# BK5811.net
KiCad netlist of a schematic drawn in Altium Designer
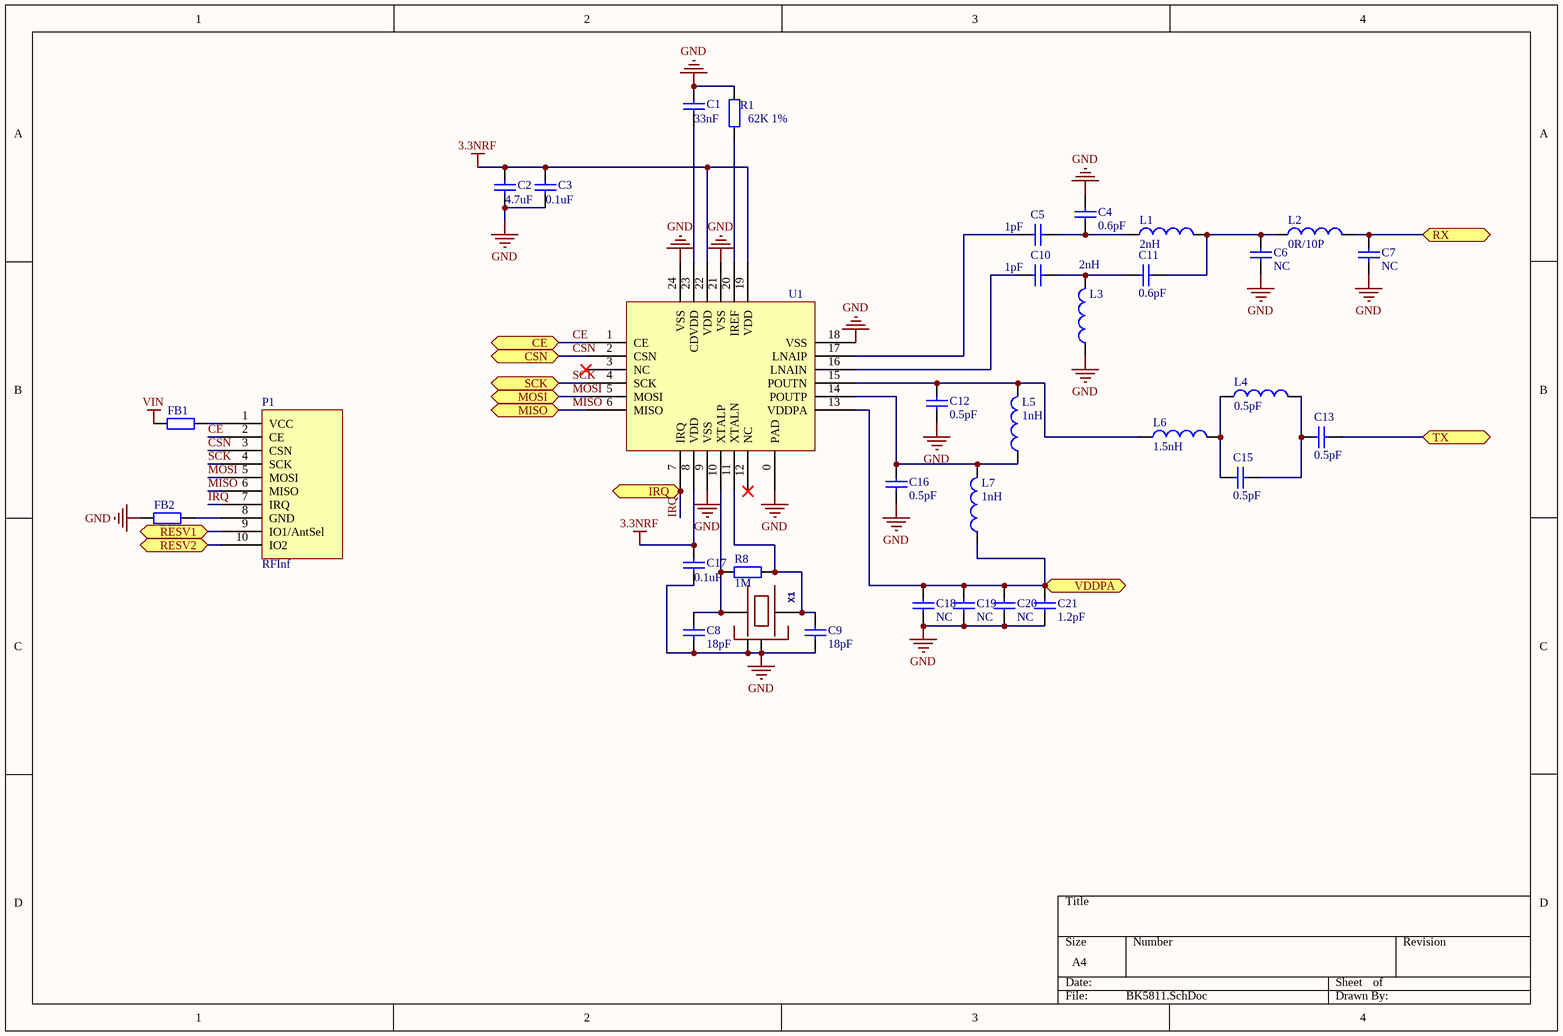
[diagram p0: BK5811.SchDoc]

(export (version "E")
  (design (tool "Eeschema 10.0.6"))
  (components
    (comp (ref "C1")
      (value "33nF")
      (footprint "0402")
      (description "Capacitor")
      (fields (field (name "PUBLISHER") "Altium Limited"))
      (libsource (lib "RTC6705") (part "Cap"))
    )
    (comp (ref "C2")
      (value "4.7uF")
      (footprint "0603")
      (description "Capacitor")
      (fields (field (name "PUBLISHER") "Altium Limited"))
      (libsource (lib "RTC6705") (part "Cap"))
    )
    (comp (ref "C3")
      (value "0.1uF")
      (footprint "0402")
      (description "Capacitor")
      (fields (field (name "PUBLISHER") "Altium Limited"))
      (libsource (lib "RTC6705") (part "Cap"))
    )
    (comp (ref "C4")
      (value "0.6pF")
      (footprint "0402")
      (description "Capacitor")
      (fields (field (name "PUBLISHER") "Altium Limited"))
      (libsource (lib "RTC6705") (part "Cap"))
    )
    (comp (ref "C5")
      (value "1pF")
      (footprint "0402")
      (description "Capacitor")
      (fields (field (name "PUBLISHER") "Altium Limited"))
      (libsource (lib "RTC6705") (part "Cap"))
    )
    (comp (ref "C6")
      (value "NC")
      (footprint "0402")
      (description "Capacitor")
      (fields (field (name "PUBLISHER") "Altium Limited"))
      (libsource (lib "RTC6705") (part "Cap"))
    )
    (comp (ref "C7")
      (value "NC")
      (footprint "0402")
      (description "Capacitor")
      (fields (field (name "PUBLISHER") "Altium Limited"))
      (libsource (lib "RTC6705") (part "Cap"))
    )
    (comp (ref "C8")
      (value "18pF")
      (footprint "0402")
      (description "Capacitor")
      (fields (field (name "Comment") "Cap") (field (name "PUBLISHER") "Altium Limited"))
      (libsource (lib "RTC6705") (part "Cap"))
    )
    (comp (ref "C9")
      (value "18pF")
      (footprint "0402")
      (description "Capacitor")
      (fields (field (name "Comment") "Cap") (field (name "PUBLISHER") "Altium Limited"))
      (libsource (lib "RTC6705") (part "Cap"))
    )
    (comp (ref "C10")
      (value "1pF")
      (footprint "0402")
      (description "Capacitor")
      (fields (field (name "PUBLISHER") "Altium Limited"))
      (libsource (lib "RTC6705") (part "Cap"))
    )
    (comp (ref "C11")
      (value "0.6pF")
      (footprint "0402")
      (description "Capacitor")
      (fields (field (name "PUBLISHER") "Altium Limited"))
      (libsource (lib "RTC6705") (part "Cap"))
    )
    (comp (ref "C12")
      (value "0.5pF")
      (footprint "0402")
      (description "Capacitor")
      (fields (field (name "PUBLISHER") "Altium Limited"))
      (libsource (lib "RTC6705") (part "Cap"))
    )
    (comp (ref "C13")
      (value "0.5pF")
      (footprint "0402")
      (description "Capacitor")
      (fields (field (name "PUBLISHER") "Altium Limited"))
      (libsource (lib "RTC6705") (part "Cap"))
    )
    (comp (ref "C15")
      (value "0.5pF")
      (footprint "0402")
      (description "Capacitor")
      (fields (field (name "PUBLISHER") "Altium Limited"))
      (libsource (lib "RTC6705") (part "Cap"))
    )
    (comp (ref "C16")
      (value "0.5pF")
      (footprint "0402")
      (description "Capacitor")
      (fields (field (name "PUBLISHER") "Altium Limited"))
      (libsource (lib "RTC6705") (part "Cap"))
    )
    (comp (ref "C17")
      (value "0.1uF")
      (footprint "0402")
      (description "Capacitor")
      (fields (field (name "PUBLISHER") "Altium Limited"))
      (libsource (lib "RTC6705") (part "Cap"))
    )
    (comp (ref "C18")
      (value "NC")
      (footprint "0402")
      (description "Capacitor")
      (fields (field (name "PUBLISHER") "Altium Limited"))
      (libsource (lib "RTC6705") (part "Cap"))
    )
    (comp (ref "C19")
      (value "NC")
      (footprint "0402")
      (description "Capacitor")
      (fields (field (name "PUBLISHER") "Altium Limited"))
      (libsource (lib "RTC6705") (part "Cap"))
    )
    (comp (ref "C20")
      (value "NC")
      (footprint "0402")
      (description "Capacitor")
      (fields (field (name "PUBLISHER") "Altium Limited"))
      (libsource (lib "RTC6705") (part "Cap"))
    )
    (comp (ref "C21")
      (value "1.2pF")
      (footprint "0402")
      (description "Capacitor")
      (fields (field (name "PUBLISHER") "Altium Limited"))
      (libsource (lib "RTC6705") (part "Cap"))
    )
    (comp (ref "FB1")
      (value "Res2")
      (footprint "0402")
      (description "Resistor")
      (fields (field (name "PUBLISHER") "Altium Limited"))
      (libsource (lib "RTC6705") (part "Res2"))
    )
    (comp (ref "FB2")
      (value "Res2")
      (footprint "0402")
      (description "Resistor")
      (fields (field (name "PUBLISHER") "Altium Limited"))
      (libsource (lib "RTC6705") (part "Res2"))
    )
    (comp (ref "L1")
      (value "2nH")
      (footprint "0402")
      (description "Inductor")
      (fields (field (name "PUBLISHER") "Altium Limited"))
      (libsource (lib "Miscellaneous Devices") (part "Inductor"))
    )
    (comp (ref "L2")
      (value "0R/10P")
      (footprint "0402")
      (description "Inductor")
      (fields (field (name "PUBLISHER") "Altium Limited"))
      (libsource (lib "Miscellaneous Devices") (part "Inductor"))
    )
    (comp (ref "L3")
      (value "2nH")
      (footprint "0402")
      (description "Inductor")
      (fields (field (name "PUBLISHER") "Altium Limited"))
      (libsource (lib "Miscellaneous Devices") (part "Inductor"))
    )
    (comp (ref "L4")
      (value "0.5pF")
      (footprint "0402")
      (description "Inductor")
      (fields (field (name "PUBLISHER") "Altium Limited"))
      (libsource (lib "Miscellaneous Devices") (part "Inductor"))
    )
    (comp (ref "L5")
      (value "1nH")
      (footprint "0402")
      (description "Inductor")
      (fields (field (name "PUBLISHER") "Altium Limited"))
      (libsource (lib "Miscellaneous Devices") (part "Inductor"))
    )
    (comp (ref "L6")
      (value "1.5nH")
      (footprint "0402")
      (description "Inductor")
      (fields (field (name "PUBLISHER") "Altium Limited"))
      (libsource (lib "Miscellaneous Devices") (part "Inductor"))
    )
    (comp (ref "L7")
      (value "1nH")
      (footprint "0402")
      (description "Inductor")
      (fields (field (name "PUBLISHER") "Altium Limited"))
      (libsource (lib "Miscellaneous Devices") (part "Inductor"))
    )
    (comp (ref "P1")
      (value "RFInf")
      (footprint "RFInf - SINGLESIDE")
      (libsource (lib "NRF24L01_PA") (part "RFInf"))
    )
    (comp (ref "R1")
      (value "62K 1%")
      (footprint "0402")
      (description "Resistor")
      (fields (field (name "PUBLISHER") "Altium Limited"))
      (libsource (lib "") (part "Res2_1"))
    )
    (comp (ref "R8")
      (value "1M")
      (footprint "0402")
      (description "Resistor")
      (fields (field (name "Comment") "Res2") (field (name "PUBLISHER") "Altium Limited"))
      (libsource (lib "") (part "Res2_2"))
    )
    (comp (ref "U1") (value "BK5811") (footprint "BK5811") (libsource (lib "BK5811") (part "BK5811")))
    (comp (ref "X1")
      (value "16Mhz")
      (footprint "OSCILLATOR-3.2X2.5")
      (description "Crystal Oscillator in 3.2x2.5 SMD")
      (libsource (lib "pixhawk2") (part "OSCILLATOR-3.2X2.5"))
    )
  )
  (nets
    (net (code "1") (name "/CE") (class "Default")
      (node (ref "P1") (pin "2") (pinfunction "CE_2") (pintype "passive"))
      (node (ref "U1") (pin "1") (pinfunction "CE_1") (pintype "passive"))
    )
    (net (code "2") (name "/CSN") (class "Default")
      (node (ref "P1") (pin "3") (pinfunction "CSN_3") (pintype "passive"))
      (node (ref "U1") (pin "2") (pinfunction "CSN_2") (pintype "passive"))
    )
    (net (code "3") (name "/IRQ") (class "Default")
      (node (ref "P1") (pin "7") (pinfunction "IRQ_7") (pintype "passive"))
      (node (ref "U1") (pin "7") (pinfunction "IRQ_7") (pintype "passive"))
    )
    (net (code "4") (name "/MISO") (class "Default")
      (node (ref "P1") (pin "6") (pinfunction "MISO_6") (pintype "passive"))
      (node (ref "U1") (pin "6") (pinfunction "MISO_6") (pintype "passive"))
    )
    (net (code "5") (name "/MOSI") (class "Default")
      (node (ref "P1") (pin "5") (pinfunction "MOSI_5") (pintype "passive"))
      (node (ref "U1") (pin "5") (pinfunction "MOSI_5") (pintype "passive"))
    )
    (net (code "6") (name "/RESV1") (class "Default")
      (node (ref "P1") (pin "9") (pinfunction "IO1/AntSel_9") (pintype "passive"))
    )
    (net (code "7") (name "/RESV2") (class "Default")
      (node (ref "P1") (pin "10") (pinfunction "IO2_10") (pintype "passive"))
    )
    (net (code "8") (name "/RX") (class "Default")
      (node (ref "C7") (pin "2") (pinfunction "2_2") (pintype "passive"))
      (node (ref "L2") (pin "2") (pinfunction "2_2") (pintype "passive"))
    )
    (net (code "9") (name "/SCK") (class "Default")
      (node (ref "P1") (pin "4") (pinfunction "SCK_4") (pintype "passive"))
      (node (ref "U1") (pin "4") (pinfunction "SCK_4") (pintype "passive"))
    )
    (net (code "10") (name "/TX") (class "Default")
      (node (ref "C13") (pin "2") (pinfunction "2_2") (pintype "passive"))
    )
    (net (code "11") (name "/VDDPA") (class "Default")
      (node (ref "C18") (pin "1") (pinfunction "1_1") (pintype "passive"))
      (node (ref "C19") (pin "1") (pinfunction "1_1") (pintype "passive"))
      (node (ref "C20") (pin "1") (pinfunction "1_1") (pintype "passive"))
      (node (ref "C21") (pin "1") (pinfunction "1_1") (pintype "passive"))
      (node (ref "L7") (pin "1") (pinfunction "1_1") (pintype "passive"))
      (node (ref "U1") (pin "13") (pinfunction "VDDPA_13") (pintype "passive"))
    )
    (net (code "12") (name "3.3NRF") (class "Default")
      (node (ref "C17") (pin "2") (pinfunction "2_2") (pintype "passive"))
      (node (ref "C2") (pin "2") (pinfunction "2_2") (pintype "passive"))
      (node (ref "C3") (pin "2") (pinfunction "2_2") (pintype "passive"))
      (node (ref "U1") (pin "19") (pinfunction "VDD_19") (pintype "passive"))
      (node (ref "U1") (pin "22") (pinfunction "VDD_22") (pintype "passive"))
      (node (ref "U1") (pin "8") (pinfunction "VDD_8") (pintype "passive"))
    )
    (net (code "13") (name "GND") (class "Default")
      (node (ref "C1") (pin "2") (pinfunction "2_2") (pintype "passive"))
      (node (ref "C12") (pin "1") (pinfunction "1_1") (pintype "passive"))
      (node (ref "C16") (pin "1") (pinfunction "1_1") (pintype "passive"))
      (node (ref "C17") (pin "1") (pinfunction "1_1") (pintype "passive"))
      (node (ref "C18") (pin "2") (pinfunction "2_2") (pintype "passive"))
      (node (ref "C19") (pin "2") (pinfunction "2_2") (pintype "passive"))
      (node (ref "C2") (pin "1") (pinfunction "1_1") (pintype "passive"))
      (node (ref "C20") (pin "2") (pinfunction "2_2") (pintype "passive"))
      (node (ref "C21") (pin "2") (pinfunction "2_2") (pintype "passive"))
      (node (ref "C3") (pin "1") (pinfunction "1_1") (pintype "passive"))
      (node (ref "C4") (pin "2") (pinfunction "2_2") (pintype "passive"))
      (node (ref "C6") (pin "1") (pinfunction "1_1") (pintype "passive"))
      (node (ref "C7") (pin "1") (pinfunction "1_1") (pintype "passive"))
      (node (ref "C8") (pin "2") (pinfunction "2_2") (pintype "passive"))
      (node (ref "C9") (pin "2") (pinfunction "2_2") (pintype "passive"))
      (node (ref "FB2") (pin "1") (pinfunction "1_1") (pintype "passive"))
      (node (ref "L3") (pin "1") (pinfunction "1_1") (pintype "passive"))
      (node (ref "R1") (pin "2") (pinfunction "2_2") (pintype "passive"))
      (node (ref "U1") (pin "0") (pinfunction "PAD_0") (pintype "passive"))
      (node (ref "U1") (pin "18") (pinfunction "VSS_18") (pintype "passive"))
      (node (ref "U1") (pin "21") (pinfunction "VSS_21") (pintype "passive"))
      (node (ref "U1") (pin "24") (pinfunction "VSS_24") (pintype "passive"))
      (node (ref "U1") (pin "9") (pinfunction "VSS_9") (pintype "passive"))
      (node (ref "X1") (pin "2") (pinfunction "NC_2_2") (pintype "open_emitter"))
      (node (ref "X1") (pin "4") (pinfunction "NC_4_4") (pintype "open_emitter"))
    )
    (net (code "14") (name "Net-(C4-Pad1)") (class "Default")
      (node (ref "C4") (pin "1") (pinfunction "1_1") (pintype "passive"))
      (node (ref "C5") (pin "2") (pinfunction "2_2") (pintype "passive"))
      (node (ref "L1") (pin "1") (pinfunction "1_1") (pintype "passive"))
    )
    (net (code "15") (name "Net-(C10-Pad2)") (class "Default")
      (node (ref "C10") (pin "2") (pinfunction "2_2") (pintype "passive"))
      (node (ref "C11") (pin "2") (pinfunction "2_2") (pintype "passive"))
      (node (ref "L3") (pin "2") (pinfunction "2_2") (pintype "passive"))
    )
    (net (code "16") (name "Net-(C11-Pad1)") (class "Default")
      (node (ref "C11") (pin "1") (pinfunction "1_1") (pintype "passive"))
      (node (ref "C6") (pin "2") (pinfunction "2_2") (pintype "passive"))
      (node (ref "L1") (pin "2") (pinfunction "2_2") (pintype "passive"))
      (node (ref "L2") (pin "1") (pinfunction "1_1") (pintype "passive"))
    )
    (net (code "17") (name "Net-(C13-Pad1)") (class "Default")
      (node (ref "C13") (pin "1") (pinfunction "1_1") (pintype "passive"))
      (node (ref "C15") (pin "2") (pinfunction "2_2") (pintype "passive"))
      (node (ref "L4") (pin "2") (pinfunction "2_2") (pintype "passive"))
    )
    (net (code "18") (name "Net-(C15-Pad1)") (class "Default")
      (node (ref "C15") (pin "1") (pinfunction "1_1") (pintype "passive"))
      (node (ref "L4") (pin "1") (pinfunction "1_1") (pintype "passive"))
      (node (ref "L6") (pin "2") (pinfunction "2_2") (pintype "passive"))
    )
    (net (code "19") (name "Net-(P1-GND)") (class "Default")
      (node (ref "FB2") (pin "2") (pinfunction "2_2") (pintype "passive"))
      (node (ref "P1") (pin "8") (pinfunction "GND_8") (pintype "passive"))
    )
    (net (code "20") (name "Net-(P1-VCC)") (class "Default")
      (node (ref "FB1") (pin "2") (pinfunction "2_2") (pintype "passive"))
      (node (ref "P1") (pin "1") (pinfunction "VCC_1") (pintype "passive"))
    )
    (net (code "21") (name "Net-(U1-CDVDD)") (class "Default")
      (node (ref "C1") (pin "1") (pinfunction "1_1") (pintype "passive"))
      (node (ref "U1") (pin "23") (pinfunction "CDVDD_23") (pintype "passive"))
    )
    (net (code "22") (name "Net-(U1-IREF)") (class "Default")
      (node (ref "R1") (pin "1") (pinfunction "1_1") (pintype "passive"))
      (node (ref "U1") (pin "20") (pinfunction "IREF_20") (pintype "passive"))
    )
    (net (code "23") (name "Net-(U1-LNAIN)") (class "Default")
      (node (ref "C10") (pin "1") (pinfunction "1_1") (pintype "passive"))
      (node (ref "U1") (pin "16") (pinfunction "LNAIN_16") (pintype "passive"))
    )
    (net (code "24") (name "Net-(U1-LNAIP)") (class "Default")
      (node (ref "C5") (pin "1") (pinfunction "1_1") (pintype "passive"))
      (node (ref "U1") (pin "17") (pinfunction "LNAIP_17") (pintype "passive"))
    )
    (net (code "25") (name "Net-(U1-POUTN)") (class "Default")
      (node (ref "C12") (pin "2") (pinfunction "2_2") (pintype "passive"))
      (node (ref "L5") (pin "2") (pinfunction "2_2") (pintype "passive"))
      (node (ref "L6") (pin "1") (pinfunction "1_1") (pintype "passive"))
      (node (ref "U1") (pin "15") (pinfunction "POUTN_15") (pintype "passive"))
    )
    (net (code "26") (name "Net-(U1-POUTP)") (class "Default")
      (node (ref "C16") (pin "2") (pinfunction "2_2") (pintype "passive"))
      (node (ref "L5") (pin "1") (pinfunction "1_1") (pintype "passive"))
      (node (ref "L7") (pin "2") (pinfunction "2_2") (pintype "passive"))
      (node (ref "U1") (pin "14") (pinfunction "POUTP_14") (pintype "passive"))
    )
    (net (code "27") (name "Net-(U1-XTALN)") (class "Default")
      (node (ref "C9") (pin "1") (pinfunction "1_1") (pintype "passive"))
      (node (ref "R8") (pin "1") (pinfunction "1_1") (pintype "passive"))
      (node (ref "U1") (pin "11") (pinfunction "XTALN_11") (pintype "passive"))
      (node (ref "X1") (pin "3") (pinfunction "3_3") (pintype "passive"))
    )
    (net (code "28") (name "Net-(U1-XTALP)") (class "Default")
      (node (ref "C8") (pin "1") (pinfunction "1_1") (pintype "passive"))
      (node (ref "R8") (pin "2") (pinfunction "2_2") (pintype "passive"))
      (node (ref "U1") (pin "10") (pinfunction "XTALP_10") (pintype "passive"))
      (node (ref "X1") (pin "1") (pinfunction "1_1") (pintype "passive"))
    )
    (net (code "29") (name "VIN") (class "Default")
      (node (ref "FB1") (pin "1") (pinfunction "1_1") (pintype "passive"))
    )
    (net (code "30") (name "unconnected-(U1-NC-Pad3)") (class "Default")
      (node (ref "U1") (pin "3") (pinfunction "NC_3") (pintype "passive+no_connect"))
    )
    (net (code "31") (name "unconnected-(U1-NC-Pad12)") (class "Default")
      (node (ref "U1") (pin "12") (pinfunction "NC_12") (pintype "passive+no_connect"))
    )
  )
)
